# design.net
KiCad netlist of a schematic drawn in Altium Designer
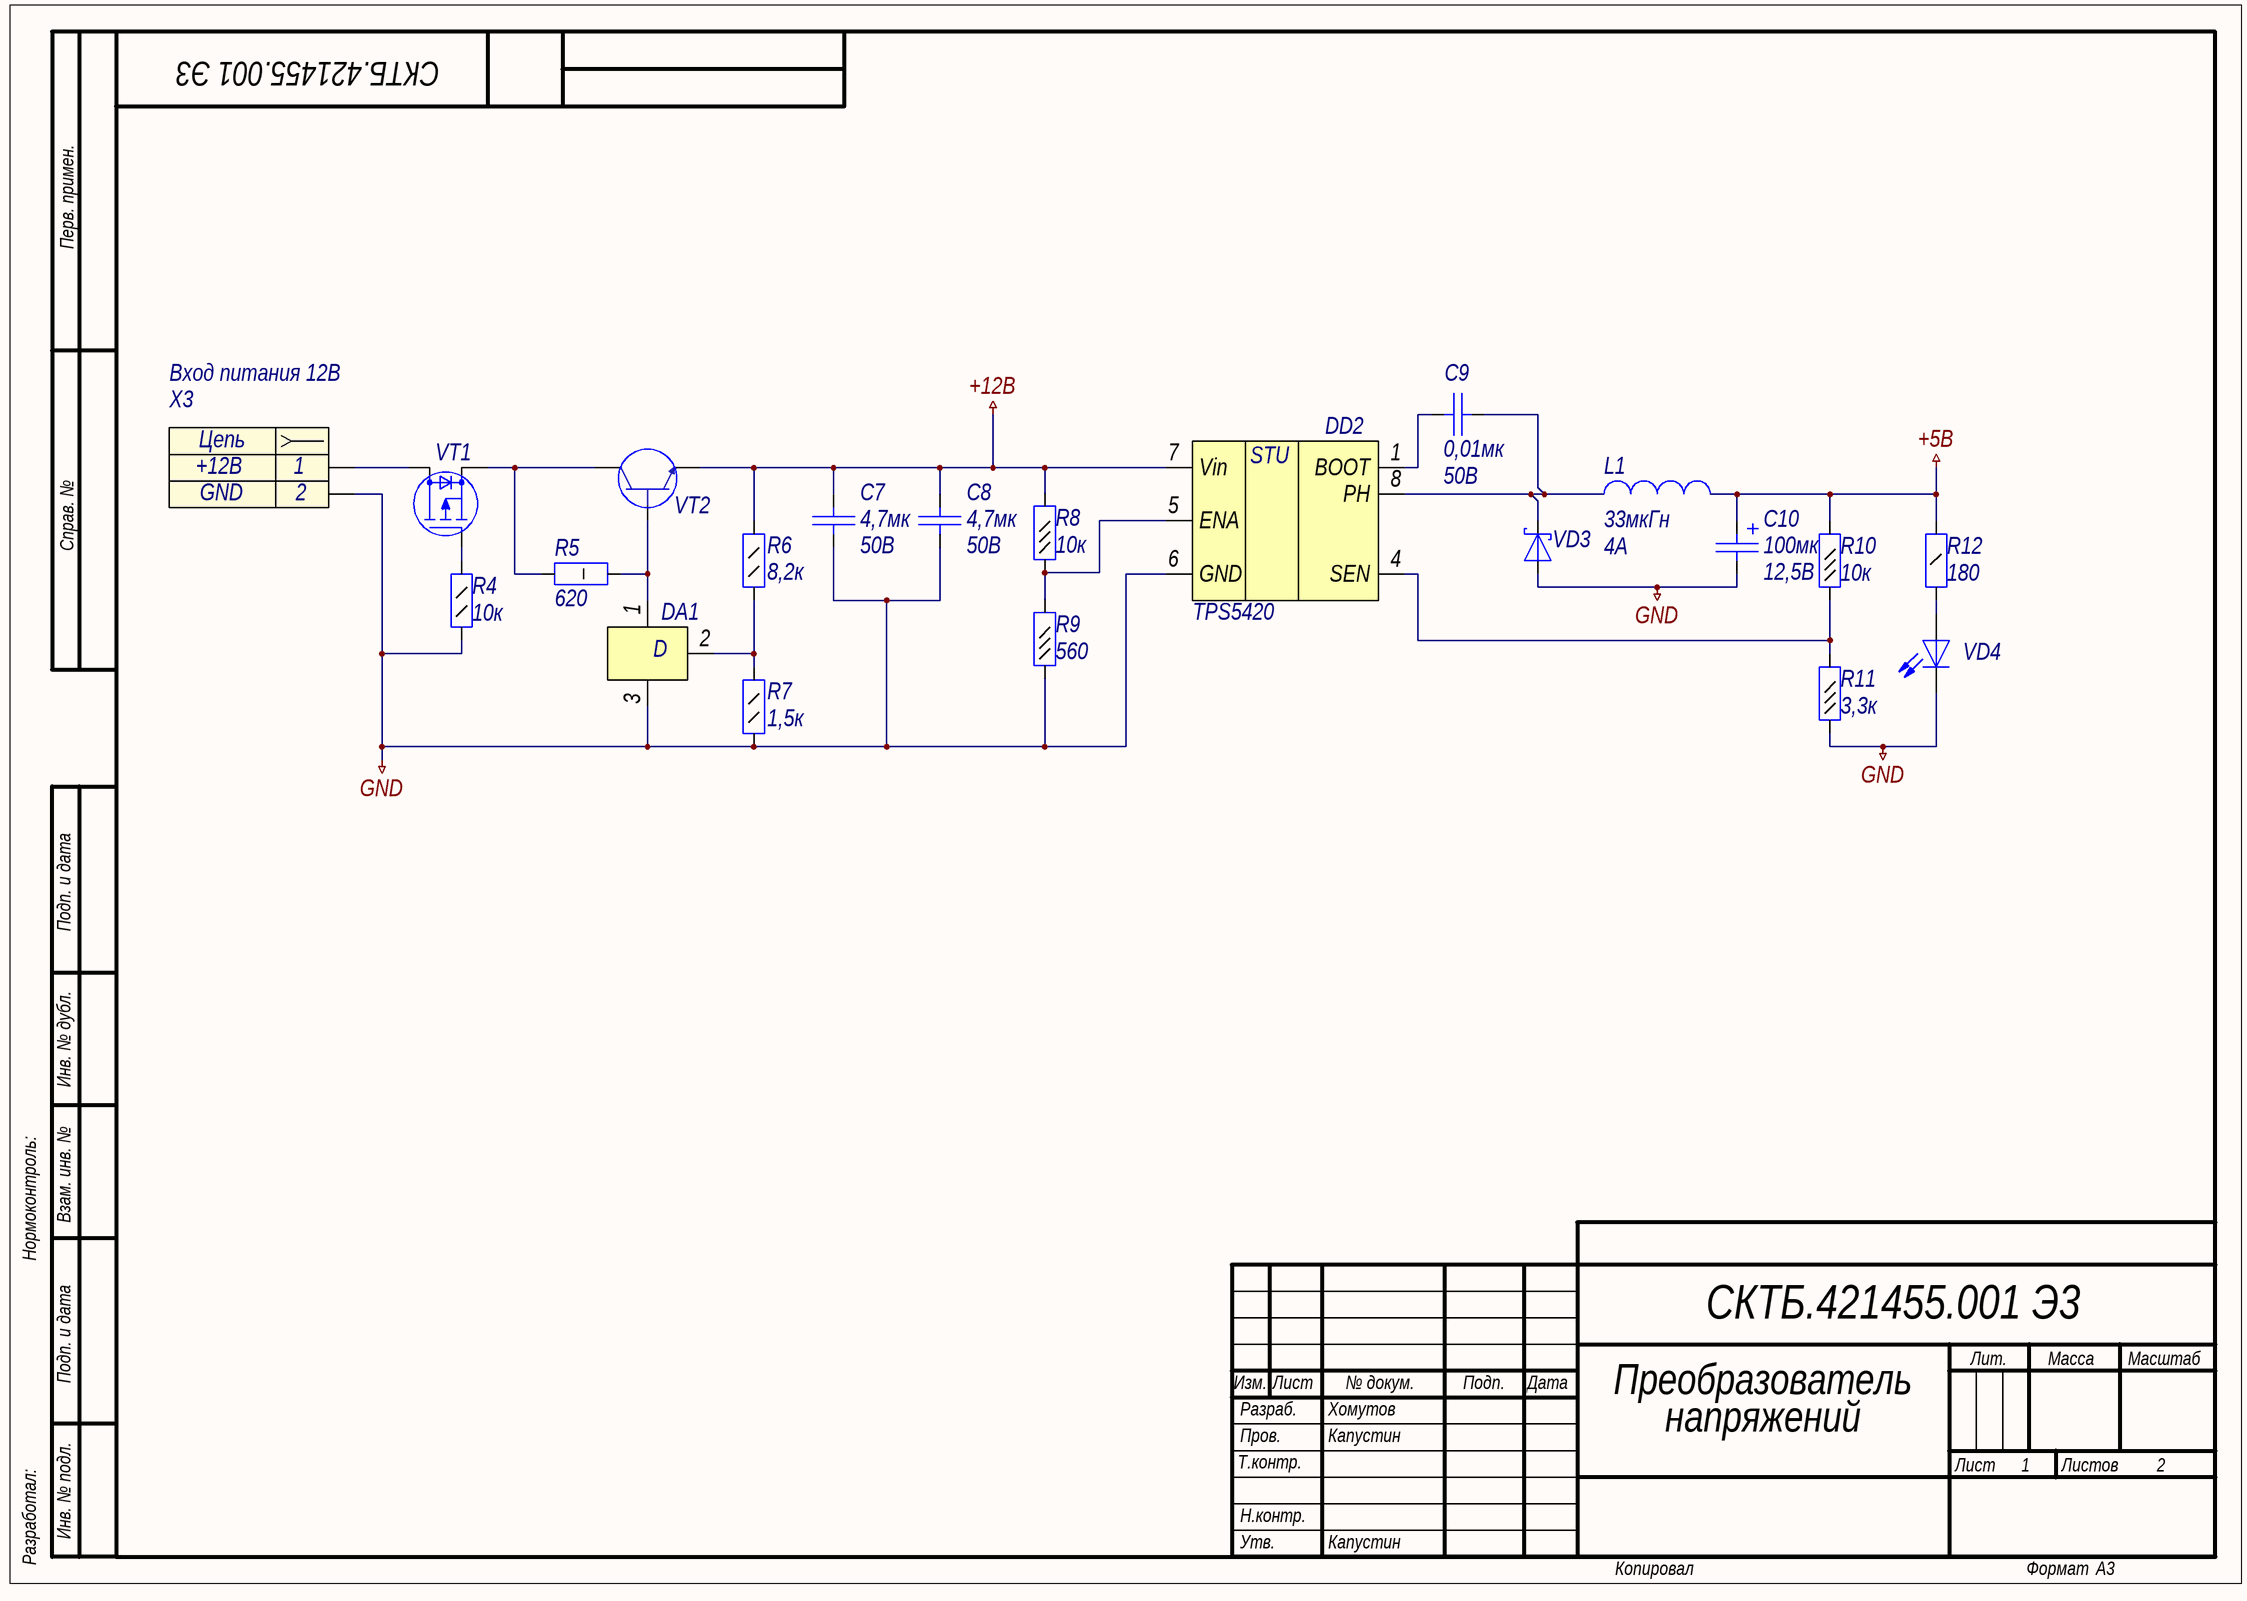
[diagram p0: Преобразователь напряжения.SchDoc]

(export (version "E")
  (design (tool "Eeschema 10.0.6"))
  (components
    (comp (ref "C7")
      (value "4,7мк")
      (footprint "C1206")
      (description "Конденсатор")
      (fields
        (field (name "VOLTAGE") "50В")
        (field (name "PART NUMBER") "GRM31CR71H475KA12L")
        (field (name "Comment") "Capacitor")
      )
      (libsource (lib "MOP44") (part "Capacitor"))
    )
    (comp (ref "C8")
      (value "4,7мк")
      (footprint "C1206")
      (description "Конденсатор")
      (fields
        (field (name "VOLTAGE") "50В")
        (field (name "PART NUMBER") "GRM31CR71H475KA12L")
        (field (name "Comment") "Capacitor")
      )
      (libsource (lib "MOP44") (part "Capacitor"))
    )
    (comp (ref "C9")
      (value "0,01мк")
      (footprint "C0402")
      (description "Конденсатор")
      (fields
        (field (name "VOLTAGE") "50B")
        (field (name "PART NUMBER") "GRM155R71H103K")
        (field (name "Comment") "Capacitor")
      )
      (libsource (lib "MOP44") (part "Capacitor"))
    )
    (comp (ref "C10")
      (value "100мк")
      (footprint "TANTAL CASE E")
      (description "Конденсатор полярный")
      (fields
        (field (name "VOLTAGE") "12,5В")
        (field (name "PART NUMBER") "ECASD91B107M012K00")
        (field (name "Comment") "Capacitor_pol")
      )
      (libsource (lib "MOP44") (part "Capacitor_pol"))
    )
    (comp (ref "DA1")
      (value "TL431")
      (footprint "SOT23-3")
      (description "Программируемый стабилитрон")
      (fields (field (name "PART NUMBER") "TL431ACDBZR"))
      (libsource (lib "MOP44") (part "TL431"))
    )
    (comp (ref "DD2")
      (value "TPS5420")
      (footprint "SO8")
      (description "2-A, WIDE INPUT RANGE, STEP-DOWN CONVERTER")
      (fields (field (name "MANUFACTURER") "Texas Instruments"))
      (libsource (lib "MOP44") (part "TPS5420"))
    )
    (comp (ref "L1")
      (value "33мкГн")
      (footprint "L4040")
      (description "EMI Suppression Filter")
      (fields
        (field (name "RATED CURRENT") "4A")
        (field (name "PART NUMBER") "IHLP4040DZER330M11")
        (field (name "Comment") "Inductor")
      )
      (libsource (lib "MOP44") (part "Inductor"))
    )
    (comp (ref "R4")
      (value "10к")
      (footprint "R0805")
      (description "Резистор")
      (fields (field (name "PART NUMBER") "RC0805FR-07100KL") (field (name "POWER") "0,125Вт"))
      (libsource (lib "MOP44") (part "Resistor_0,125Вт"))
    )
    (comp (ref "R5")
      (value "620")
      (footprint "R2512")
      (description "Резистор")
      (fields (field (name "PART NUMBER") "RC2512FR-07620RL") (field (name "POWER") "1Вт"))
      (libsource (lib "MOP44") (part "Resistor_1Вт"))
    )
    (comp (ref "R6")
      (value "8,2к")
      (footprint "R0805")
      (description "Резистор")
      (fields (field (name "PART NUMBER") "RC0805FR-078K2") (field (name "POWER") "0,125Вт"))
      (libsource (lib "MOP44") (part "Resistor_0,125Вт"))
    )
    (comp (ref "R7")
      (value "1,5к")
      (footprint "R0805")
      (description "Резистор")
      (fields (field (name "PART NUMBER") "RC0805FR-071K5") (field (name "POWER") "0,125Вт"))
      (libsource (lib "MOP44") (part "Resistor_0,125Вт"))
    )
    (comp (ref "R8")
      (value "10к")
      (footprint "R0402")
      (description "Резистор")
      (fields (field (name "PART NUMBER") "RC0402FR-0710KL") (field (name "POWER") "0,062Вт"))
      (libsource (lib "MOP44") (part "Resistor_0,062Вт"))
    )
    (comp (ref "R9")
      (value "560")
      (footprint "R0402")
      (description "Резистор")
      (fields (field (name "PART NUMBER") "RC0402FR-07560RL") (field (name "POWER") "0,062Вт"))
      (libsource (lib "MOP44") (part "Resistor_0,062Вт"))
    )
    (comp (ref "R10")
      (value "10к")
      (footprint "R0402")
      (description "Резистор")
      (fields (field (name "PART NUMBER") "RC0402FR-0710KL") (field (name "POWER") "0,062Вт"))
      (libsource (lib "MOP44") (part "Resistor_0,062Вт"))
    )
    (comp (ref "R11")
      (value "3,3к")
      (footprint "R0402")
      (description "Резистор")
      (fields (field (name "PART NUMBER") "RC0402FR-072K3") (field (name "POWER") "0,062Вт"))
      (libsource (lib "MOP44") (part "Resistor_0,062Вт"))
    )
    (comp (ref "R12")
      (value "180")
      (footprint "R1206")
      (description "Резистор")
      (fields (field (name "PART NUMBER") "RC1206FR-07180RL") (field (name "POWER") "0,25Вт"))
      (libsource (lib "MOP44") (part "Resistor_0,25Вт"))
    )
    (comp (ref "VD3")
      (value "DiodeSchottky")
      (footprint "SMA")
      (description "Диод Шоттки")
      (fields (field (name "PART NUMBER") "SK34A"))
      (libsource (lib "MOP44") (part "DiodeSchottky"))
    )
    (comp (ref "VD4")
      (value "LED")
      (footprint "L_0805")
      (description "Светодиод")
      (fields (field (name "PART NUMBER") "KP-2012EC"))
      (libsource (lib "MOP44") (part "LED"))
    )
    (comp (ref "VT1")
      (value "P-MOSFET")
      (footprint "HD-1")
      (description "N-MOSFET")
      (fields (field (name "PART NUMBER") "IRFD9024PBF") (field (name "MANUFACTURER") "Vishay"))
      (libsource (lib "MOP44") (part "P-MOSFET"))
    )
    (comp (ref "VT2")
      (value "BJT NPN")
      (footprint "SOT-223")
      (fields (field (name "POWER") "2Вт") (field (name "PART NUMBER") "PBSS4540Z.115"))
      (libsource (lib "MOP44") (part "BJT NPN"))
    )
    (comp (ref "X3")
      (value "Вход питания 12В")
      (footprint "DS-210")
      (description "Разъем - 2 конт. розетка")
      (fields (field (name "PART NUMBER") "DS-210B(PBT)(NB)"))
      (libsource (lib "MOP44") (part "Header_2_sct"))
    )
  )
  (nets
    (net (code "1") (name "+5В") (class "Default")
      (node (ref "C10") (pin "1") (pinfunction "1_1") (pintype "passive"))
      (node (ref "L1") (pin "2") (pinfunction "2_2") (pintype "passive"))
      (node (ref "R10") (pin "2") (pinfunction "2_2") (pintype "passive"))
      (node (ref "R12") (pin "2") (pinfunction "2_2") (pintype "passive"))
    )
    (net (code "2") (name "+12В") (class "Default")
      (node (ref "C7") (pin "2") (pinfunction "2_2") (pintype "passive"))
      (node (ref "C8") (pin "2") (pinfunction "2_2") (pintype "passive"))
      (node (ref "DD2") (pin "7") (pinfunction "Vin_7") (pintype "passive"))
      (node (ref "R6") (pin "2") (pinfunction "2_2") (pintype "passive"))
      (node (ref "R8") (pin "2") (pinfunction "2_2") (pintype "passive"))
      (node (ref "VT2") (pin "2") (pinfunction "2_2") (pintype "passive"))
    )
    (net (code "3") (name "GND") (class "Default")
      (node (ref "C10") (pin "2") (pinfunction "2_2") (pintype "passive"))
      (node (ref "C7") (pin "1") (pinfunction "1_1") (pintype "passive"))
      (node (ref "C8") (pin "1") (pinfunction "1_1") (pintype "passive"))
      (node (ref "DA1") (pin "3") (pinfunction "3_3") (pintype "passive"))
      (node (ref "DD2") (pin "6") (pinfunction "GND_6") (pintype "passive"))
      (node (ref "R11") (pin "1") (pinfunction "1_1") (pintype "passive"))
      (node (ref "R4") (pin "1") (pinfunction "1_1") (pintype "passive"))
      (node (ref "R7") (pin "1") (pinfunction "1_1") (pintype "passive"))
      (node (ref "R9") (pin "1") (pinfunction "1_1") (pintype "passive"))
      (node (ref "VD3") (pin "2") (pinfunction "A_2") (pintype "passive"))
      (node (ref "VD4") (pin "1") (pinfunction "K_1") (pintype "passive"))
      (node (ref "X3") (pin "2") (pinfunction "2_2") (pintype "passive"))
    )
    (net (code "4") (name "Net-(DA1-Pad2)") (class "Default")
      (node (ref "DA1") (pin "2") (pinfunction "2_2") (pintype "passive"))
      (node (ref "R6") (pin "1") (pinfunction "1_1") (pintype "passive"))
      (node (ref "R7") (pin "2") (pinfunction "2_2") (pintype "passive"))
    )
    (net (code "5") (name "Net-(DD2-BOOT)") (class "Default")
      (node (ref "C9") (pin "2") (pinfunction "2_2") (pintype "passive"))
      (node (ref "DD2") (pin "1") (pinfunction "BOOT_1") (pintype "passive"))
    )
    (net (code "6") (name "Net-(DD2-ENA)") (class "Default")
      (node (ref "DD2") (pin "5") (pinfunction "ENA_5") (pintype "passive"))
      (node (ref "R8") (pin "1") (pinfunction "1_1") (pintype "passive"))
      (node (ref "R9") (pin "2") (pinfunction "2_2") (pintype "passive"))
    )
    (net (code "7") (name "Net-(DD2-PH)") (class "Default")
      (node (ref "C9") (pin "1") (pinfunction "1_1") (pintype "passive"))
      (node (ref "DD2") (pin "8") (pinfunction "PH_8") (pintype "passive"))
      (node (ref "L1") (pin "1") (pinfunction "1_1") (pintype "passive"))
      (node (ref "VD3") (pin "1") (pinfunction "K_1") (pintype "passive"))
    )
    (net (code "8") (name "Net-(DD2-SEN)") (class "Default")
      (node (ref "DD2") (pin "4") (pinfunction "SEN_4") (pintype "passive"))
      (node (ref "R10") (pin "1") (pinfunction "1_1") (pintype "passive"))
      (node (ref "R11") (pin "2") (pinfunction "2_2") (pintype "passive"))
    )
    (net (code "9") (name "Net-(R5-5)") (class "Default")
      (node (ref "DA1") (pin "1") (pinfunction "1_1") (pintype "passive"))
      (node (ref "R5") (pin "2") (pinfunction "5_2") (pintype "passive"))
      (node (ref "VT2") (pin "1") (pinfunction "1_1") (pintype "passive"))
    )
    (net (code "10") (name "Net-(VD4-A)") (class "Default")
      (node (ref "R12") (pin "1") (pinfunction "1_1") (pintype "passive"))
      (node (ref "VD4") (pin "2") (pinfunction "A_2") (pintype "passive"))
    )
    (net (code "11") (name "Net-(VT1-D)") (class "Default")
      (node (ref "VT1") (pin "3") (pinfunction "D_3") (pintype "passive"))
      (node (ref "X3") (pin "1") (pinfunction "1_1") (pintype "passive"))
    )
    (net (code "12") (name "Net-(VT1-G)") (class "Default")
      (node (ref "R4") (pin "2") (pinfunction "2_2") (pintype "passive"))
      (node (ref "VT1") (pin "1") (pinfunction "G_1") (pintype "passive"))
    )
    (net (code "13") (name "Net-(VT1-S)") (class "Default")
      (node (ref "R5") (pin "1") (pinfunction "1_1") (pintype "passive"))
      (node (ref "VT1") (pin "2") (pinfunction "S_2") (pintype "passive"))
      (node (ref "VT2") (pin "3") (pinfunction "3_3") (pintype "passive"))
    )
  )
)
